# nano_v1_1.net
KiCad netlist of a schematic drawn in EAGLE
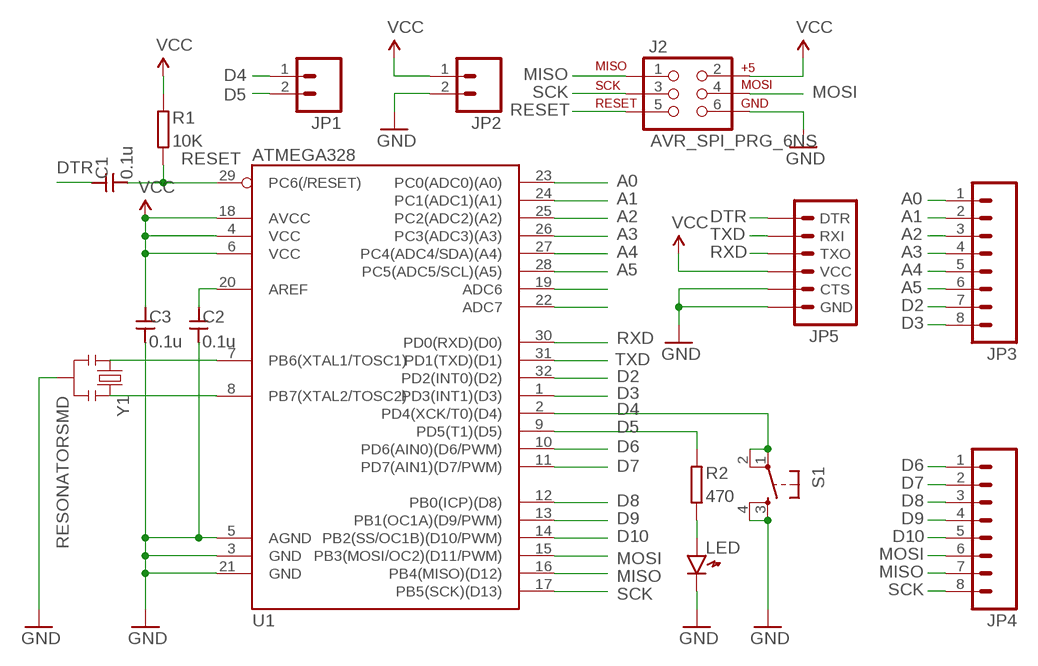
[diagram p0: schematic, sheet 1]

(export (version "E")
  (design (tool "Eeschema 10.0.6"))
  (components
    (comp (ref "C1")
      (value "0.1u")
      (footprint "eagle-import:SMD1608")
      (libsource (lib "eagle-import") (part "CAPACITOR1608"))
    )
    (comp (ref "C2")
      (value "0.1u")
      (footprint "eagle-import:SMD1608")
      (libsource (lib "eagle-import") (part "CAPACITOR1608"))
    )
    (comp (ref "C3")
      (value "0.1u")
      (footprint "eagle-import:SMD1608")
      (libsource (lib "eagle-import") (part "CAPACITOR1608"))
    )
    (comp (ref "J2")
      (value "AVR_SPI_PRG_6NS")
      (footprint "eagle-import:2X3-NS")
      (libsource (lib "eagle-import") (part "AVR_SPI_PRG_6NS"))
    )
    (comp (ref "JP1")
      (value "M02PTH")
      (footprint "eagle-import:1X02")
      (libsource (lib "eagle-import") (part "M02PTH"))
    )
    (comp (ref "JP2")
      (value "M02PTH")
      (footprint "eagle-import:1X02")
      (libsource (lib "eagle-import") (part "M02PTH"))
    )
    (comp (ref "JP3")
      (value "M081X08")
      (footprint "eagle-import:1X08")
      (libsource (lib "eagle-import") (part "M081X08"))
    )
    (comp (ref "JP4")
      (value "M081X08")
      (footprint "eagle-import:1X08")
      (libsource (lib "eagle-import") (part "M081X08"))
    )
    (comp (ref "JP5")
      (value "ARDUINO_SERIAL_PROGRAMPTH")
      (footprint "eagle-import:1X06")
      (libsource (lib "eagle-import") (part "ARDUINO_SERIAL_PROGRAMPTH"))
    )
    (comp (ref "LED")
      (value "LED1608")
      (footprint "eagle-import:LED1608")
      (libsource (lib "eagle-import") (part "LED1608"))
    )
    (comp (ref "R1")
      (value "10K")
      (footprint "eagle-import:SMD1608")
      (libsource (lib "eagle-import") (part "REGISTOR1608"))
    )
    (comp (ref "R2")
      (value "470")
      (footprint "eagle-import:SMD1608")
      (libsource (lib "eagle-import") (part "REGISTOR1608"))
    )
    (comp (ref "S1")
      (value "TAC_SWITCHSMD")
      (footprint "eagle-import:TACTILE_SWITCH_SMD")
      (libsource (lib "eagle-import") (part "TAC_SWITCHSMD"))
    )
    (comp (ref "U1")
      (value "ATMEGA328")
      (footprint "eagle-import:TQFP32-08")
      (libsource (lib "eagle-import") (part "ATMEGA328"))
    )
    (comp (ref "Y1")
      (value "RESONATORSMD")
      (footprint "eagle-import:RESONATOR-SMD")
      (libsource (lib "eagle-import") (part "RESONATORSMD"))
    )
  )
  (nets
    (net (code "1") (name "/A0") (class "Default")
      (node (ref "JP3") (pin "1") (pinfunction "1_1") (pintype "passive"))
      (node (ref "U1") (pin "23") (pinfunction "PC0(ADC0)(A0)_23") (pintype "bidirectional"))
    )
    (net (code "2") (name "/A1") (class "Default")
      (node (ref "JP3") (pin "2") (pinfunction "2_2") (pintype "passive"))
      (node (ref "U1") (pin "24") (pinfunction "PC1(ADC1)(A1)_24") (pintype "bidirectional"))
    )
    (net (code "3") (name "/A2") (class "Default")
      (node (ref "JP3") (pin "3") (pinfunction "3_3") (pintype "passive"))
      (node (ref "U1") (pin "25") (pinfunction "PC2(ADC2)(A2)_25") (pintype "bidirectional"))
    )
    (net (code "4") (name "/A3") (class "Default")
      (node (ref "JP3") (pin "4") (pinfunction "4_4") (pintype "passive"))
      (node (ref "U1") (pin "26") (pinfunction "PC3(ADC3)(A3)_26") (pintype "bidirectional"))
    )
    (net (code "5") (name "/A4") (class "Default")
      (node (ref "JP3") (pin "5") (pinfunction "5_5") (pintype "passive"))
      (node (ref "U1") (pin "27") (pinfunction "PC4(ADC4/SDA)(A4)_27") (pintype "bidirectional"))
    )
    (net (code "6") (name "/A5") (class "Default")
      (node (ref "JP3") (pin "6") (pinfunction "6_6") (pintype "passive"))
      (node (ref "U1") (pin "28") (pinfunction "PC5(ADC5/SCL)(A5)_28") (pintype "bidirectional"))
    )
    (net (code "7") (name "/D2") (class "Default")
      (node (ref "JP3") (pin "7") (pinfunction "7_7") (pintype "passive"))
      (node (ref "U1") (pin "32") (pinfunction "PD2(INT0)(D2)_32") (pintype "bidirectional"))
    )
    (net (code "8") (name "/D3") (class "Default")
      (node (ref "JP3") (pin "8") (pinfunction "8_8") (pintype "passive"))
      (node (ref "U1") (pin "1") (pinfunction "PD3(INT1)(D3)_1") (pintype "bidirectional"))
    )
    (net (code "9") (name "/D4") (class "Default")
      (node (ref "JP1") (pin "1") (pinfunction "1_1") (pintype "passive"))
      (node (ref "S1") (pin "1") (pinfunction "1_1") (pintype "passive"))
      (node (ref "S1") (pin "2") (pinfunction "2_2") (pintype "passive"))
      (node (ref "U1") (pin "2") (pinfunction "PD4(XCK/T0)(D4)_2") (pintype "bidirectional"))
    )
    (net (code "10") (name "/D5") (class "Default")
      (node (ref "JP1") (pin "2") (pinfunction "2_2") (pintype "passive"))
      (node (ref "R2") (pin "1") (pinfunction "1_1") (pintype "passive"))
      (node (ref "U1") (pin "9") (pinfunction "PD5(T1)(D5)_9") (pintype "bidirectional"))
    )
    (net (code "11") (name "/D6") (class "Default")
      (node (ref "JP4") (pin "1") (pinfunction "1_1") (pintype "passive"))
      (node (ref "U1") (pin "10") (pinfunction "PD6(AIN0)(D6/PWM)_10") (pintype "bidirectional"))
    )
    (net (code "12") (name "/D7") (class "Default")
      (node (ref "JP4") (pin "2") (pinfunction "2_2") (pintype "passive"))
      (node (ref "U1") (pin "11") (pinfunction "PD7(AIN1)(D7/PWM)_11") (pintype "bidirectional"))
    )
    (net (code "13") (name "/D8") (class "Default")
      (node (ref "JP4") (pin "3") (pinfunction "3_3") (pintype "passive"))
      (node (ref "U1") (pin "12") (pinfunction "PB0(ICP)(D8)_12") (pintype "bidirectional"))
    )
    (net (code "14") (name "/D9") (class "Default")
      (node (ref "JP4") (pin "4") (pinfunction "4_4") (pintype "passive"))
      (node (ref "U1") (pin "13") (pinfunction "PB1(OC1A)(D9/PWM)_13") (pintype "bidirectional"))
    )
    (net (code "15") (name "/D10") (class "Default")
      (node (ref "JP4") (pin "5") (pinfunction "5_5") (pintype "passive"))
      (node (ref "U1") (pin "14") (pinfunction "PB2(SS/OC1B)(D10/PWM)_14") (pintype "bidirectional"))
    )
    (net (code "16") (name "/DTR") (class "Default")
      (node (ref "C1") (pin "1") (pinfunction "1_1") (pintype "passive"))
      (node (ref "JP5") (pin "1") (pinfunction "DTR_1") (pintype "passive"))
    )
    (net (code "17") (name "/MISO") (class "Default")
      (node (ref "J2") (pin "1") (pinfunction "1_1") (pintype "passive"))
      (node (ref "JP4") (pin "7") (pinfunction "7_7") (pintype "passive"))
      (node (ref "U1") (pin "16") (pinfunction "PB4(MISO)(D12)_16") (pintype "bidirectional"))
    )
    (net (code "18") (name "/MOSI") (class "Default")
      (node (ref "J2") (pin "4") (pinfunction "4_4") (pintype "passive"))
      (node (ref "JP4") (pin "6") (pinfunction "6_6") (pintype "passive"))
      (node (ref "U1") (pin "15") (pinfunction "PB3(MOSI/OC2)(D11/PWM)_15") (pintype "bidirectional"))
    )
    (net (code "19") (name "/RESET") (class "Default")
      (node (ref "C1") (pin "2") (pinfunction "2_2") (pintype "passive"))
      (node (ref "J2") (pin "5") (pinfunction "5_5") (pintype "passive"))
      (node (ref "R1") (pin "2") (pinfunction "2_2") (pintype "passive"))
      (node (ref "U1") (pin "29") (pinfunction "PC6(/RESET)_29") (pintype "bidirectional"))
    )
    (net (code "20") (name "/RXD") (class "Default")
      (node (ref "JP5") (pin "3") (pinfunction "TXO_3") (pintype "passive"))
      (node (ref "U1") (pin "30") (pinfunction "PD0(RXD)(D0)_30") (pintype "bidirectional"))
    )
    (net (code "21") (name "/SCK") (class "Default")
      (node (ref "J2") (pin "3") (pinfunction "3_3") (pintype "passive"))
      (node (ref "JP4") (pin "8") (pinfunction "8_8") (pintype "passive"))
      (node (ref "U1") (pin "17") (pinfunction "PB5(SCK)(D13)_17") (pintype "bidirectional"))
    )
    (net (code "22") (name "/TXD") (class "Default")
      (node (ref "JP5") (pin "2") (pinfunction "RXI_2") (pintype "passive"))
      (node (ref "U1") (pin "31") (pinfunction "PD1(TXD)(D1)_31") (pintype "bidirectional"))
    )
    (net (code "23") (name "GND") (class "Default")
      (node (ref "C2") (pin "2") (pinfunction "2_2") (pintype "passive"))
      (node (ref "C3") (pin "2") (pinfunction "2_2") (pintype "passive"))
      (node (ref "J2") (pin "6") (pinfunction "6_6") (pintype "passive"))
      (node (ref "JP2") (pin "2") (pinfunction "2_2") (pintype "passive"))
      (node (ref "JP5") (pin "5") (pinfunction "CTS_5") (pintype "passive"))
      (node (ref "JP5") (pin "6") (pinfunction "GND_6") (pintype "passive"))
      (node (ref "LED") (pin "K") (pinfunction "K_K") (pintype "passive"))
      (node (ref "S1") (pin "3") (pinfunction "3_3") (pintype "passive"))
      (node (ref "S1") (pin "4") (pinfunction "4_4") (pintype "passive"))
      (node (ref "U1") (pin "21") (pinfunction "GND_21") (pintype "bidirectional"))
      (node (ref "U1") (pin "3") (pinfunction "GND_3") (pintype "bidirectional"))
      (node (ref "U1") (pin "5") (pinfunction "AGND_5") (pintype "bidirectional"))
      (node (ref "Y1") (pin "2") (pinfunction "2_2") (pintype "passive"))
    )
    (net (code "24") (name "Net-(LED-PadA)") (class "Default")
      (node (ref "LED") (pin "A") (pinfunction "A_A") (pintype "passive"))
      (node (ref "R2") (pin "2") (pinfunction "2_2") (pintype "passive"))
    )
    (net (code "25") (name "Net-(U1-AREF)") (class "Default")
      (node (ref "C2") (pin "1") (pinfunction "1_1") (pintype "passive"))
      (node (ref "U1") (pin "20") (pinfunction "AREF_20") (pintype "bidirectional"))
    )
    (net (code "26") (name "Net-(U1-PB6(XTAL1{slash}TOSC1))") (class "Default")
      (node (ref "U1") (pin "7") (pinfunction "PB6(XTAL1/TOSC1)_7") (pintype "bidirectional"))
      (node (ref "Y1") (pin "1") (pinfunction "1_1") (pintype "passive"))
    )
    (net (code "27") (name "Net-(U1-PB7(XTAL2{slash}TOSC2))") (class "Default")
      (node (ref "U1") (pin "8") (pinfunction "PB7(XTAL2/TOSC2)_8") (pintype "bidirectional"))
      (node (ref "Y1") (pin "3") (pinfunction "3_3") (pintype "passive"))
    )
    (net (code "28") (name "VCC") (class "Default")
      (node (ref "C3") (pin "1") (pinfunction "1_1") (pintype "passive"))
      (node (ref "J2") (pin "2") (pinfunction "2_2") (pintype "passive"))
      (node (ref "JP2") (pin "1") (pinfunction "1_1") (pintype "passive"))
      (node (ref "JP5") (pin "4") (pinfunction "VCC_4") (pintype "passive"))
      (node (ref "R1") (pin "1") (pinfunction "1_1") (pintype "passive"))
      (node (ref "U1") (pin "18") (pinfunction "AVCC_18") (pintype "bidirectional"))
      (node (ref "U1") (pin "4") (pinfunction "VCC_4") (pintype "bidirectional"))
      (node (ref "U1") (pin "6") (pinfunction "VCC_6") (pintype "bidirectional"))
    )
    (net (code "29") (name "unconnected-(U1-ADC6-Pad19)") (class "Default")
      (node (ref "U1") (pin "19") (pinfunction "ADC6_19") (pintype "bidirectional"))
    )
    (net (code "30") (name "unconnected-(U1-ADC7-Pad22)") (class "Default")
      (node (ref "U1") (pin "22") (pinfunction "ADC7_22") (pintype "bidirectional"))
    )
  )
)
